# 07_-_POWER.net
KiCad netlist of a schematic drawn in Altium Designer
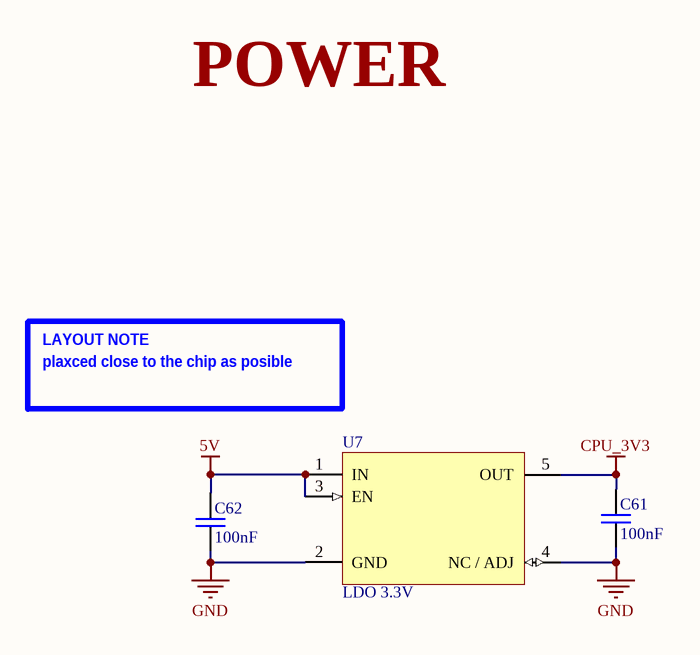
[diagram p0: [07] - POWER.SchDoc]

(export (version "E")
  (design (tool "Eeschema 10.0.6"))
  (components
    (comp (ref "C61")
      (value "100nF")
      (footprint "C0603")
      (description "C0603")
      (fields (field (name "Comment") "02016D104KAT2A"))
      (libsource (lib "Passive components") (part "02016D104KAT2A"))
    )
    (comp (ref "C62")
      (value "100nF")
      (footprint "C0603")
      (description "C0603")
      (fields (field (name "Comment") "02016D104KAT2A"))
      (libsource (lib "Passive components") (part "02016D104KAT2A"))
    )
    (comp (ref "U7")
      (value "LDO 3.3V")
      (footprint "NCV8161BSN330T1G")
      (description "LDO fixed 3.3V 450mA ultra-low noise")
      (libsource (lib "Voltage regulators") (part "NCV8161BSN330T1G"))
    )
  )
  (nets
    (net (code "1") (name "5V") (class "Default")
      (node (ref "C62") (pin "2") (pinfunction "2_2") (pintype "passive"))
      (node (ref "U7") (pin "1") (pinfunction "IN_1") (pintype "power_in"))
      (node (ref "U7") (pin "3") (pinfunction "EN_3") (pintype "input"))
    )
    (net (code "2") (name "CPU_3V3") (class "Default")
      (node (ref "C61") (pin "2") (pinfunction "2_2") (pintype "passive"))
      (node (ref "U7") (pin "5") (pinfunction "OUT_5") (pintype "power_in"))
    )
    (net (code "3") (name "GND") (class "Default")
      (node (ref "C61") (pin "1") (pinfunction "1_1") (pintype "passive"))
      (node (ref "C62") (pin "1") (pinfunction "1_1") (pintype "passive"))
      (node (ref "U7") (pin "2") (pinfunction "GND_2") (pintype "power_in"))
      (node (ref "U7") (pin "4") (pinfunction "NC_/_ADJ_4") (pintype "bidirectional"))
    )
  )
)
